# STM32_Input.net
KiCad netlist of a schematic drawn in Altium Designer
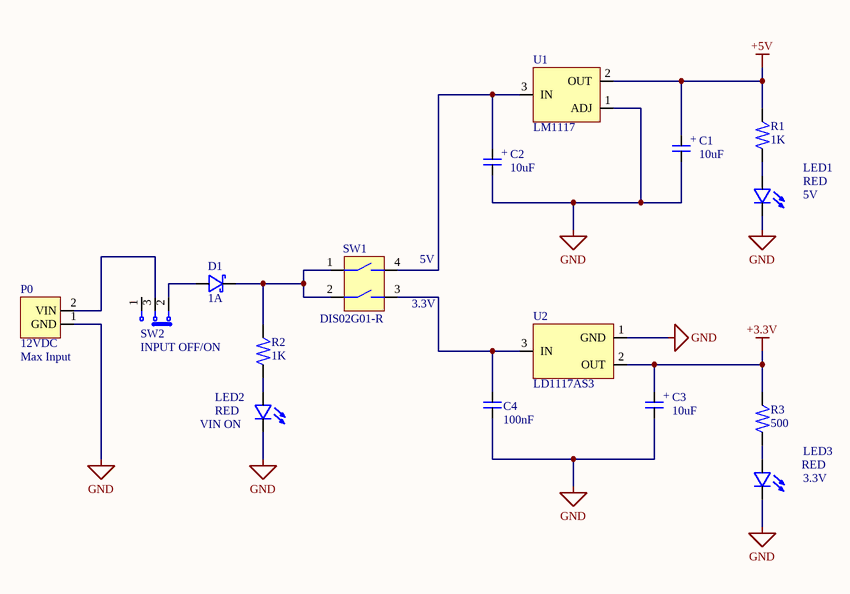
[diagram p0: STM32_Input.SchDoc]

(export (version "E")
  (design (tool "Eeschema 10.0.6"))
  (components
    (comp (ref "C1")
      (value "10uF")
      (footprint "SMT_CAP_EL_CHANG_VT1E100MC054000CE0")
      (description "SMT Capacitor Electrolytic 35V 10uF Pitch 1.3mm VT1E100MC054000CE0")
      (libsource (lib "SMT_CAP_EL_CHANG_VT1E100MC054000CE0") (part "SMT_CAP_EL_CHANG_VT1E100MC054000CE0"))
    )
    (comp (ref "C2")
      (value "10uF")
      (footprint "SMT_CAP_EL_CHANG_VT1E100MC054000CE0")
      (description "SMT Capacitor Electrolytic 35V 10uF Pitch 1.3mm VT1E100MC054000CE0")
      (libsource (lib "SMT_CAP_EL_CHANG_VT1E100MC054000CE0") (part "SMT_CAP_EL_CHANG_VT1E100MC054000CE0"))
    )
    (comp (ref "C3")
      (value "10uF")
      (footprint "SMT_CAP_EL_CHANG_VT1E100MC054000CE0")
      (description "SMT Capacitor Electrolytic 35V 10uF Pitch 1.3mm VT1E100MC054000CE0")
      (libsource (lib "SMT_CAP_EL_CHANG_VT1E100MC054000CE0") (part "SMT_CAP_EL_CHANG_VT1E100MC054000CE0"))
    )
    (comp (ref "C4")
      (value "100nF")
      (footprint "SMT_CAP_1206(3216)_SAMSUNG")
      (description "Ceramic Capacitor 1206(3216) Samsung CL31B104KBCNNNC 50VDC")
      (libsource (lib "SMT_CAP_1206(3216)_SAMSUNG") (part "SMT_CAP_1206(3216)_SAMSUNG"))
    )
    (comp (ref "D1")
      (value "1A")
      (footprint "SMT_DIODE_SCHTKY_SMB_ONSEMI")
      (description "SMT Diode Schottky ONSEMI MODEL IF=1A VR=20V FV=0.6V MBRS120T3G")
      (libsource (lib "SMT_DIODE_SCHTKY_SMB_ONSEMI") (part "SMT_DIODE_SCHTKY_SMB_ONSEMI"))
    )
    (comp (ref "LED1")
      (value "RED")
      (footprint "DIOM2012X18N")
      (description "Led Diode 0805(2012) Cathode Mark, 20mA")
      (libsource (lib "SMT_LED_0805(2012)") (part "SMT_LED_0805(2012)"))
    )
    (comp (ref "LED2")
      (value "RED")
      (footprint "DIOM2012X18N")
      (description "Led Diode 0805(2012) Cathode Mark, 20mA")
      (libsource (lib "SMT_LED_0805(2012)") (part "SMT_LED_0805(2012)"))
    )
    (comp (ref "LED3")
      (value "RED")
      (footprint "DIOM2012X18N")
      (description "Led Diode 0805(2012) Cathode Mark, 20mA")
      (libsource (lib "SMT_LED_0805(2012)") (part "SMT_LED_0805(2012)"))
    )
    (comp (ref "P0")
      (value "12VDC")
      (footprint "THT_CON_WAFER_2P_STRAIGHT_A2001WV2-2P")
      (description "Connector Wafer 2-Pins Pitch-2.0mm Straight Pins A2001WV2-2P")
      (libsource (lib "THT_CON_WAFER_2P_STRAIGHT_A2001WV2-2P") (part "THT_CON_WAFER_2P_STRAIGHT_A2001WV2-2P"))
    )
    (comp (ref "R1")
      (value "1K")
      (footprint "SMT_RES_0805(2012)")
      (description "0805(2012) Resistor 1/4-1/8W 150V 2A")
      (libsource (lib "SMT_RES_0805(2012)") (part "SMT_RES_0805(2012)"))
    )
    (comp (ref "R2")
      (value "1K")
      (footprint "SMT_RES_0805(2012)")
      (description "0805(2012) Resistor 1/4-1/8W 150V 2A")
      (libsource (lib "SMT_RES_0805(2012)") (part "SMT_RES_0805(2012)"))
    )
    (comp (ref "R3")
      (value "500")
      (footprint "SMT_RES_0805(2012)")
      (description "0805(2012) Resistor 1/4-1/8W 150V 2A")
      (libsource (lib "SMT_RES_0805(2012)") (part "SMT_RES_0805(2012)"))
    )
    (comp (ref "SW1")
      (value "DIS02G01-R")
      (footprint "SMT_SWITCH_DIP_DIS02G01-R")
      (description "DIP SMD Switch 2-Line 4-Pole 2.54Pitch Rating 25mA/24Vdc Height 0.70mm")
      (libsource (lib "SMT_SWITCH_DIP_DIS02G01-R") (part "SMT_SWITCH_DIP_DIS02G01-R"))
    )
    (comp (ref "SW2")
      (value "INPUT OFF/ON")
      (footprint "THT_SSW_ESP1010")
      (description "Slide Switch ESP1010 12V 0.5A")
      (libsource (lib "THT_SSW_ESP1010") (part "THT_SSW_ESP1010"))
    )
    (comp (ref "U1")
      (value "LM1117")
      (footprint "SOT230P700X180-4N")
      (description "LM1117 SOT-223 5V HTC Voltage Regulator")
      (libsource (lib "LM1117_SOT-223") (part "LM1117_SOT-223"))
    )
    (comp (ref "U2")
      (value "LD1117AS3")
      (footprint "SMT_VR_LD1117AS3")
      (description "Voltage Regulator ST LD1117AS33TR 1A 3.3V 10Vmax")
      (libsource (lib "SMT_VR_LD1117AS3") (part "SMT_VR_LD1117AS3"))
    )
  )
  (nets
    (net (code "1") (name "+3.3V") (class "Default")
      (node (ref "C3") (pin "1") (pinfunction "1_1") (pintype "passive"))
      (node (ref "R3") (pin "2") (pinfunction "2_2") (pintype "passive"))
      (node (ref "U2") (pin "2") (pinfunction "OUT_2") (pintype "passive"))
    )
    (net (code "2") (name "+5V") (class "Default")
      (node (ref "C1") (pin "1") (pinfunction "1_1") (pintype "passive"))
      (node (ref "R1") (pin "2") (pinfunction "2_2") (pintype "passive"))
      (node (ref "U1") (pin "2") (pinfunction "OUT_2") (pintype "passive"))
    )
    (net (code "3") (name "GND") (class "Default")
      (node (ref "C1") (pin "2") (pinfunction "2_2") (pintype "passive"))
      (node (ref "C2") (pin "2") (pinfunction "2_2") (pintype "passive"))
      (node (ref "C3") (pin "2") (pinfunction "2_2") (pintype "passive"))
      (node (ref "C4") (pin "1") (pinfunction "1_1") (pintype "passive"))
      (node (ref "LED1") (pin "2") (pinfunction "2_2") (pintype "passive"))
      (node (ref "LED2") (pin "2") (pinfunction "2_2") (pintype "passive"))
      (node (ref "LED3") (pin "2") (pinfunction "2_2") (pintype "passive"))
      (node (ref "P0") (pin "1") (pinfunction "GND_1") (pintype "passive"))
      (node (ref "U1") (pin "1") (pinfunction "ADJ_1") (pintype "passive"))
      (node (ref "U2") (pin "1") (pinfunction "GND_1") (pintype "passive"))
    )
    (net (code "4") (name "Net-(D1-Pad1)") (class "Default")
      (node (ref "D1") (pin "1") (pinfunction "1_1") (pintype "passive"))
      (node (ref "SW2") (pin "2") (pinfunction "2_2") (pintype "passive"))
    )
    (net (code "5") (name "Net-(D1-Pad2)") (class "Default")
      (node (ref "D1") (pin "2") (pinfunction "2_2") (pintype "passive"))
      (node (ref "R2") (pin "2") (pinfunction "2_2") (pintype "passive"))
      (node (ref "SW1") (pin "1") (pinfunction "1_1") (pintype "passive"))
      (node (ref "SW1") (pin "2") (pinfunction "2_2") (pintype "passive"))
    )
    (net (code "6") (name "Net-(LED1-Pad1)") (class "Default")
      (node (ref "LED1") (pin "1") (pinfunction "1_1") (pintype "passive"))
      (node (ref "R1") (pin "1") (pinfunction "1_1") (pintype "passive"))
    )
    (net (code "7") (name "Net-(LED2-Pad1)") (class "Default")
      (node (ref "LED2") (pin "1") (pinfunction "1_1") (pintype "passive"))
      (node (ref "R2") (pin "1") (pinfunction "1_1") (pintype "passive"))
    )
    (net (code "8") (name "Net-(LED3-Pad1)") (class "Default")
      (node (ref "LED3") (pin "1") (pinfunction "1_1") (pintype "passive"))
      (node (ref "R3") (pin "1") (pinfunction "1_1") (pintype "passive"))
    )
    (net (code "9") (name "Net-(P0-VIN)") (class "Default")
      (node (ref "P0") (pin "2") (pinfunction "VIN_2") (pintype "passive"))
      (node (ref "SW2") (pin "3") (pinfunction "3_3") (pintype "passive"))
    )
    (net (code "10") (name "Net-(U1-IN)") (class "Default")
      (node (ref "C2") (pin "1") (pinfunction "1_1") (pintype "passive"))
      (node (ref "SW1") (pin "4") (pinfunction "4_4") (pintype "passive"))
      (node (ref "U1") (pin "3") (pinfunction "IN_3") (pintype "passive"))
    )
    (net (code "11") (name "Net-(U2-IN)") (class "Default")
      (node (ref "C4") (pin "2") (pinfunction "2_2") (pintype "passive"))
      (node (ref "SW1") (pin "3") (pinfunction "3_3") (pintype "passive"))
      (node (ref "U2") (pin "3") (pinfunction "IN_3") (pintype "passive"))
    )
    (net (code "12") (name "unconnected-(SW2-Pad1)") (class "Default")
      (node (ref "SW2") (pin "1") (pinfunction "1_1") (pintype "passive"))
    )
  )
)
